# Sheet1.net
KiCad netlist of a schematic drawn in Altium Designer
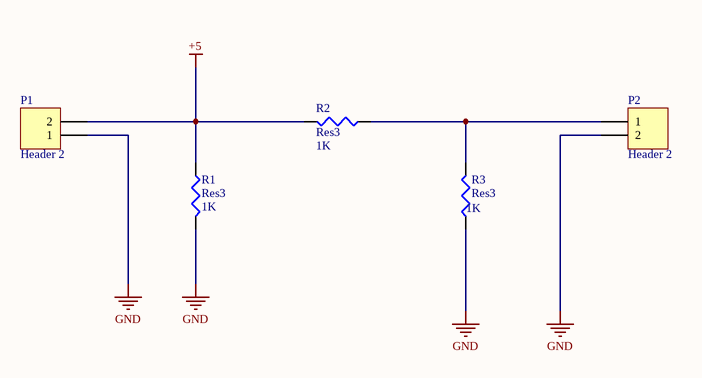
[diagram p0: Sheet1.SchDoc]

(export (version "E")
  (design (tool "Eeschema 10.0.6"))
  (components
    (comp (ref "P1")
      (value "Header 2")
      (footprint "HDR1X2")
      (description "Header, 2-Pin")
      (fields (field (name "PUBLISHER") "Altium Limited"))
      (libsource (lib "") (part "Header 2_1"))
    )
    (comp (ref "P2")
      (value "Header 2")
      (footprint "HDR1X2")
      (description "Header, 2-Pin")
      (fields (field (name "PUBLISHER") "Altium Limited"))
      (libsource (lib "Miscellaneous Connectors") (part "Header 2"))
    )
    (comp (ref "R1")
      (value "Res3")
      (footprint "J1-0603")
      (description "Resistor")
      (fields (field (name "ALTIUM_VALUE") "1K") (field (name "PUBLISHER") "Altium Limited"))
      (libsource (lib "Miscellaneous Devices") (part "Res3"))
    )
    (comp (ref "R2")
      (value "Res3")
      (footprint "J1-0603")
      (description "Resistor")
      (fields (field (name "ALTIUM_VALUE") "1K") (field (name "PUBLISHER") "Altium Limited"))
      (libsource (lib "Miscellaneous Devices") (part "Res3"))
    )
    (comp (ref "R3")
      (value "Res3")
      (footprint "J1-0603")
      (description "Resistor")
      (fields (field (name "ALTIUM_VALUE") "1K") (field (name "PUBLISHER") "Altium Limited"))
      (libsource (lib "Miscellaneous Devices") (part "Res3"))
    )
  )
  (nets
    (net (code "1") (name "+5") (class "Default")
      (node (ref "P1") (pin "2") (pinfunction "2_2") (pintype "passive"))
      (node (ref "R1") (pin "1") (pinfunction "1_1") (pintype "passive"))
      (node (ref "R2") (pin "2") (pinfunction "2_2") (pintype "passive"))
    )
    (net (code "2") (name "GND") (class "Default")
      (node (ref "P1") (pin "1") (pinfunction "1_1") (pintype "passive"))
      (node (ref "P2") (pin "2") (pinfunction "2_2") (pintype "passive"))
      (node (ref "R1") (pin "2") (pinfunction "2_2") (pintype "passive"))
      (node (ref "R3") (pin "1") (pinfunction "1_1") (pintype "passive"))
    )
    (net (code "3") (name "Net-(P2-Pad1)") (class "Default")
      (node (ref "P2") (pin "1") (pinfunction "1_1") (pintype "passive"))
      (node (ref "R2") (pin "1") (pinfunction "1_1") (pintype "passive"))
      (node (ref "R3") (pin "2") (pinfunction "2_2") (pintype "passive"))
    )
  )
)
